# rfid_module_v2.net
KiCad netlist of a schematic drawn in EAGLE
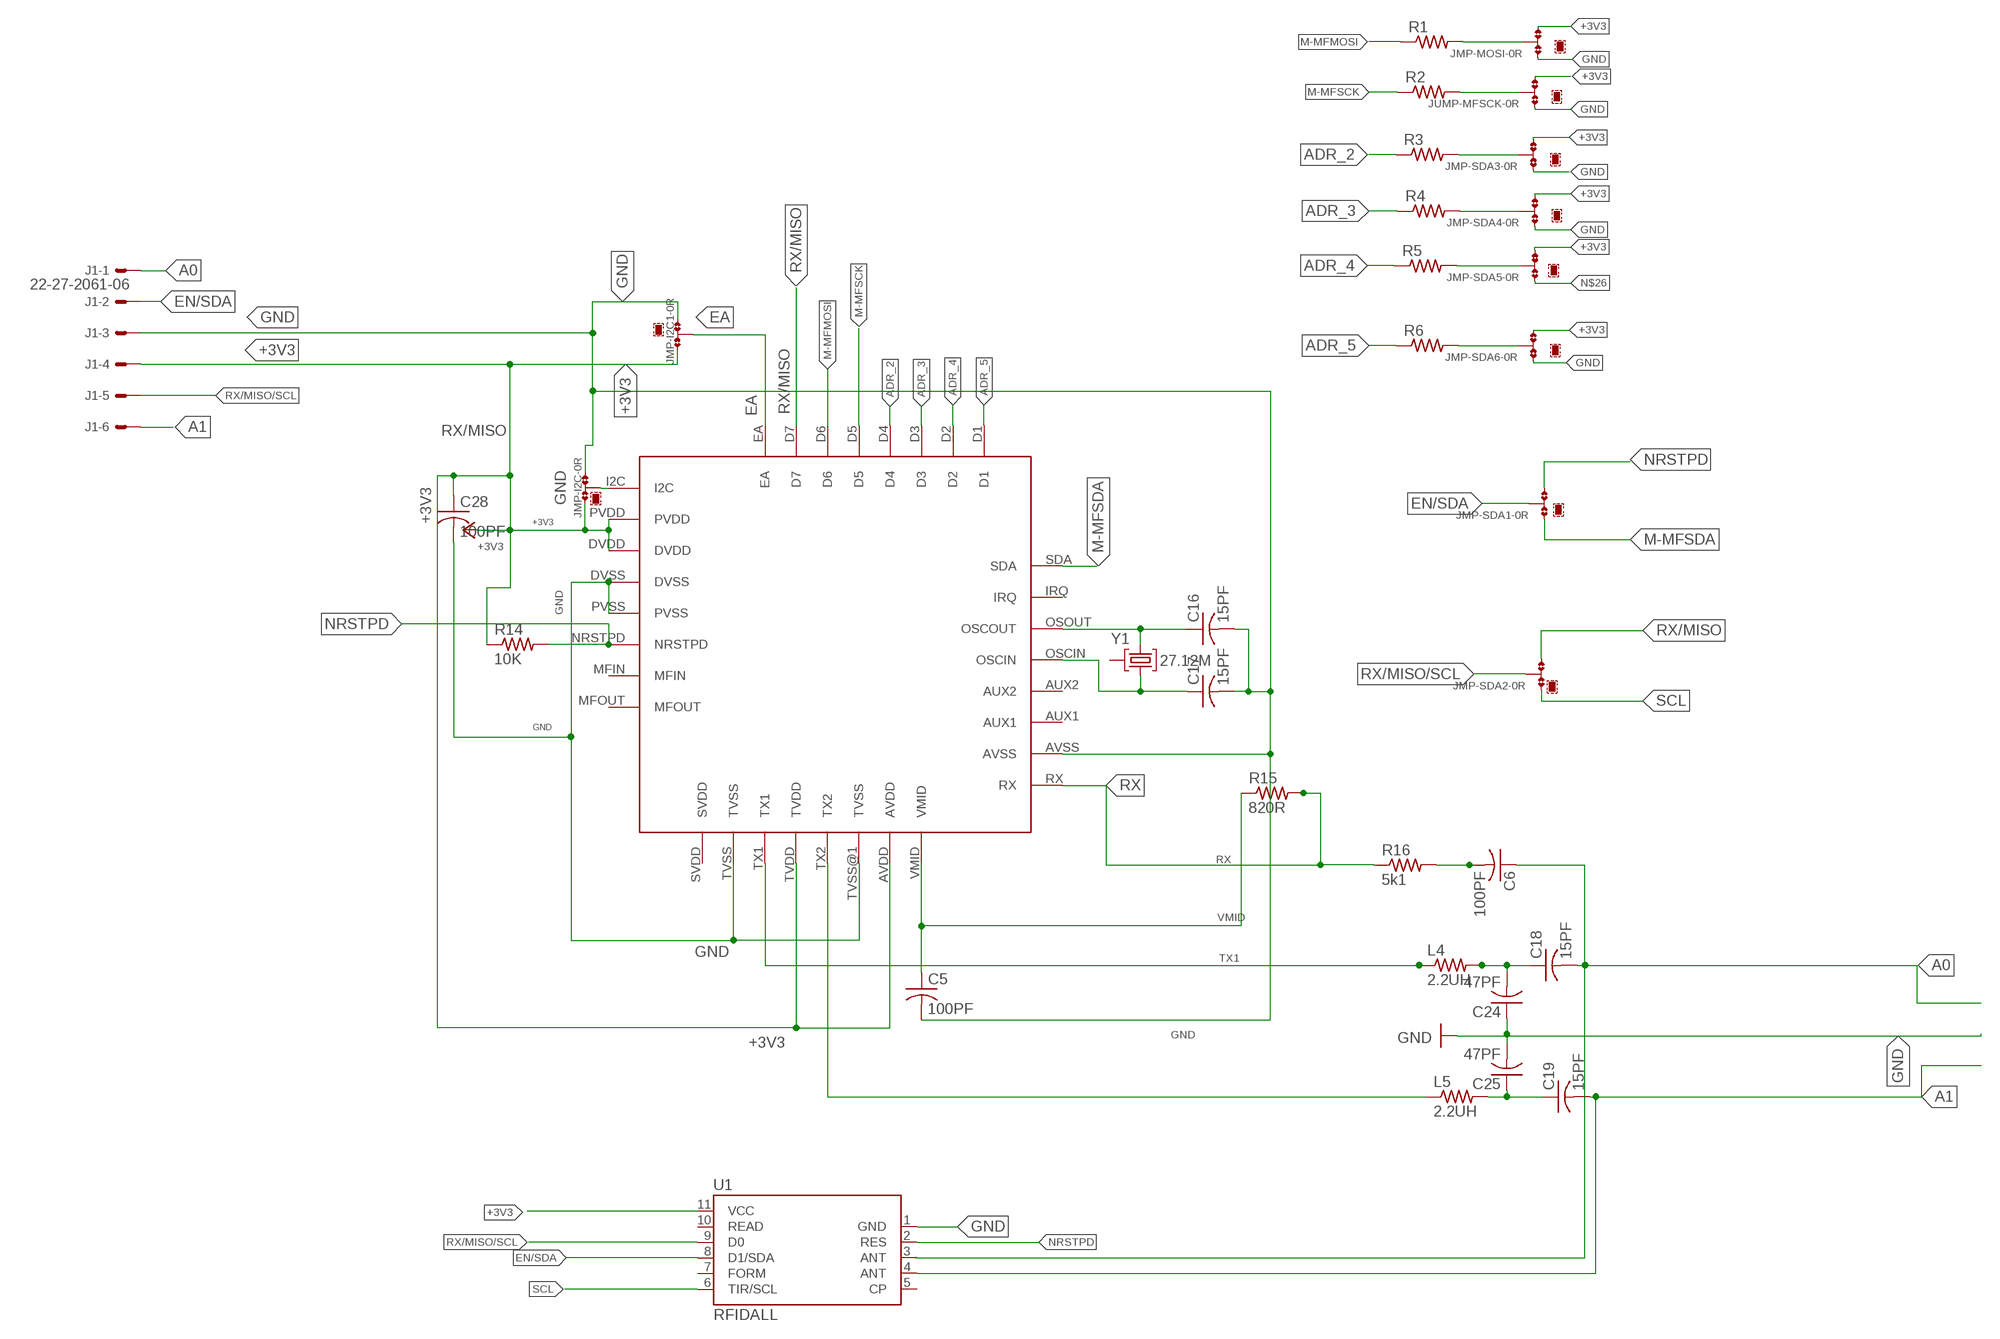
[diagram p0: schematic, sheet 1]

(export (version "E")
  (design (tool "Eeschema 10.0.6"))
  (components
    (comp (ref "C5")
      (value "100PF")
      (footprint "eagle-import:C0402")
      (libsource (lib "eagle-import") (part "C-USC0402"))
    )
    (comp (ref "C6")
      (value "100PF")
      (footprint "eagle-import:C0402")
      (libsource (lib "eagle-import") (part "C-USC0402"))
    )
    (comp (ref "C16")
      (value "15PF")
      (footprint "eagle-import:C0402")
      (libsource (lib "eagle-import") (part "C-USC0402"))
    )
    (comp (ref "C17")
      (value "15PF")
      (footprint "eagle-import:C0402")
      (libsource (lib "eagle-import") (part "C-USC0402"))
    )
    (comp (ref "C18")
      (value "15PF")
      (footprint "eagle-import:C0402")
      (libsource (lib "eagle-import") (part "C-USC0402"))
    )
    (comp (ref "C19")
      (value "15PF")
      (footprint "eagle-import:C0402")
      (libsource (lib "eagle-import") (part "C-USC0402"))
    )
    (comp (ref "C24")
      (value "47PF")
      (footprint "eagle-import:C0402")
      (libsource (lib "eagle-import") (part "C-USC0402"))
    )
    (comp (ref "C25")
      (value "47PF")
      (footprint "eagle-import:C0402")
      (libsource (lib "eagle-import") (part "C-USC0402"))
    )
    (comp (ref "C28")
      (value "100PF")
      (footprint "eagle-import:C0402")
      (libsource (lib "eagle-import") (part "C-USC0402"))
    )
    (comp (ref "J1")
      (value "22-27-2061-06")
      (footprint "eagle-import:6410-06")
      (libsource (lib "eagle-import") (part "22-?-0627-2061"))
    )
    (comp (ref "JMP-I2C")
      (value "0R-JUMPA")
      (footprint "eagle-import:A0R-JMP")
      (libsource (lib "eagle-import") (part "0R-JUMPA"))
    )
    (comp (ref "JMP-I2C1")
      (value "0R-JUMPA")
      (footprint "eagle-import:A0R-JMP")
      (libsource (lib "eagle-import") (part "0R-JUMPA"))
    )
    (comp (ref "JMP-MOSI")
      (value "0R-JUMPA")
      (footprint "eagle-import:A0R-JMP")
      (libsource (lib "eagle-import") (part "0R-JUMPA"))
    )
    (comp (ref "JMP-SDA1")
      (value "0R-JUMPA")
      (footprint "eagle-import:A0R-JMP")
      (libsource (lib "eagle-import") (part "0R-JUMPA"))
    )
    (comp (ref "JMP-SDA2")
      (value "0R-JUMPA")
      (footprint "eagle-import:A0R-JMP")
      (libsource (lib "eagle-import") (part "0R-JUMPA"))
    )
    (comp (ref "JMP-SDA3")
      (value "0R-JUMPA")
      (footprint "eagle-import:A0R-JMP")
      (libsource (lib "eagle-import") (part "0R-JUMPA"))
    )
    (comp (ref "JMP-SDA4")
      (value "0R-JUMPA")
      (footprint "eagle-import:A0R-JMP")
      (libsource (lib "eagle-import") (part "0R-JUMPA"))
    )
    (comp (ref "JMP-SDA5")
      (value "0R-JUMPA")
      (footprint "eagle-import:A0R-JMP")
      (libsource (lib "eagle-import") (part "0R-JUMPA"))
    )
    (comp (ref "JMP-SDA6")
      (value "0R-JUMPA")
      (footprint "eagle-import:A0R-JMP")
      (libsource (lib "eagle-import") (part "0R-JUMPA"))
    )
    (comp (ref "JUMP-MFSCK")
      (value "0R-JUMPA")
      (footprint "eagle-import:A0R-JMP")
      (libsource (lib "eagle-import") (part "0R-JUMPA"))
    )
    (comp (ref "L4")
      (value "2.2UH")
      (footprint "eagle-import:R0402")
      (libsource (lib "eagle-import") (part "R-US_R0402"))
    )
    (comp (ref "L5")
      (value "2.2UH")
      (footprint "eagle-import:R0402")
      (libsource (lib "eagle-import") (part "R-US_R0402"))
    )
    (comp (ref "R1")
      (value "R-US_R0402")
      (footprint "eagle-import:R0402")
      (libsource (lib "eagle-import") (part "R-US_R0402"))
    )
    (comp (ref "R2")
      (value "R-US_R0402")
      (footprint "eagle-import:R0402")
      (libsource (lib "eagle-import") (part "R-US_R0402"))
    )
    (comp (ref "R3")
      (value "R-US_R0402")
      (footprint "eagle-import:R0402")
      (libsource (lib "eagle-import") (part "R-US_R0402"))
    )
    (comp (ref "R4")
      (value "R-US_R0402")
      (footprint "eagle-import:R0402")
      (libsource (lib "eagle-import") (part "R-US_R0402"))
    )
    (comp (ref "R5")
      (value "R-US_R0402")
      (footprint "eagle-import:R0402")
      (libsource (lib "eagle-import") (part "R-US_R0402"))
    )
    (comp (ref "R6")
      (value "R-US_R0402")
      (footprint "eagle-import:R0402")
      (libsource (lib "eagle-import") (part "R-US_R0402"))
    )
    (comp (ref "R14")
      (value "10K")
      (footprint "eagle-import:R0402")
      (libsource (lib "eagle-import") (part "R-US_R0402"))
    )
    (comp (ref "R15")
      (value "820R")
      (footprint "eagle-import:R0402")
      (libsource (lib "eagle-import") (part "R-US_R0402"))
    )
    (comp (ref "R16")
      (value "5k1")
      (footprint "eagle-import:R0402")
      (libsource (lib "eagle-import") (part "R-US_R0402"))
    )
    (comp (ref "U$1")
      (value "MFRC522")
      (footprint "eagle-import:MFRC522")
      (libsource (lib "eagle-import") (part "MFRC522"))
    )
    (comp (ref "U1")
      (value "RFIDALL")
      (footprint "eagle-import:ID_PACKAGE")
      (libsource (lib "eagle-import") (part "RFIDALL"))
    )
    (comp (ref "Y1")
      (value "27.12M")
      (footprint "eagle-import:RAD3LEAD")
      (libsource (lib "eagle-import") (part "CRYSTAL"))
    )
  )
  (nets
    (net (code "1") (name "+3V3") (class "Default")
      (node (ref "C28") (pin "1") (pinfunction "1_1") (pintype "passive"))
      (node (ref "J1") (pin "4") (pinfunction "S_4") (pintype "passive"))
      (node (ref "JMP-I2C") (pin "3") (pinfunction "3_3") (pintype "passive"))
      (node (ref "JMP-I2C1") (pin "3") (pinfunction "3_3") (pintype "passive"))
      (node (ref "JMP-MOSI") (pin "3") (pinfunction "3_3") (pintype "passive"))
      (node (ref "JMP-SDA3") (pin "3") (pinfunction "3_3") (pintype "passive"))
      (node (ref "JMP-SDA4") (pin "3") (pinfunction "3_3") (pintype "passive"))
      (node (ref "JMP-SDA5") (pin "3") (pinfunction "3_3") (pintype "passive"))
      (node (ref "JMP-SDA6") (pin "3") (pinfunction "3_3") (pintype "passive"))
      (node (ref "JUMP-MFSCK") (pin "3") (pinfunction "3_3") (pintype "passive"))
      (node (ref "R14") (pin "1") (pinfunction "1_1") (pintype "passive"))
      (node (ref "U$1") (pin "AVDD") (pinfunction "AVDD_AVDD") (pintype "bidirectional"))
      (node (ref "U$1") (pin "DVDD") (pinfunction "DVDD_DVDD") (pintype "bidirectional"))
      (node (ref "U$1") (pin "PVDD") (pinfunction "PVDD_PVDD") (pintype "bidirectional"))
      (node (ref "U$1") (pin "TVDD") (pinfunction "TVDD_TVDD") (pintype "bidirectional"))
      (node (ref "U1") (pin "11") (pinfunction "VCC_11") (pintype "bidirectional"))
    )
    (net (code "2") (name "/TX1") (class "Default")
      (node (ref "L4") (pin "1") (pinfunction "1_1") (pintype "passive"))
      (node (ref "U$1") (pin "TX1") (pinfunction "TX1_TX1") (pintype "bidirectional"))
    )
    (net (code "3") (name "/VMID") (class "Default")
      (node (ref "C5") (pin "1") (pinfunction "1_1") (pintype "passive"))
      (node (ref "R15") (pin "1") (pinfunction "1_1") (pintype "passive"))
      (node (ref "U$1") (pin "VMID") (pinfunction "VMID_VMID") (pintype "bidirectional"))
    )
    (net (code "4") (name "A0") (class "Default")
      (node (ref "C18") (pin "2") (pinfunction "2_2") (pintype "passive"))
      (node (ref "C6") (pin "1") (pinfunction "1_1") (pintype "passive"))
      (node (ref "J1") (pin "1") (pinfunction "S_1") (pintype "passive"))
    )
    (net (code "5") (name "A1") (class "Default")
      (node (ref "C19") (pin "2") (pinfunction "2_2") (pintype "passive"))
      (node (ref "J1") (pin "6") (pinfunction "S_6") (pintype "passive"))
      (node (ref "U1") (pin "4") (pinfunction "ANT_4") (pintype "bidirectional"))
    )
    (net (code "6") (name "ADR_2") (class "Default")
      (node (ref "R3") (pin "1") (pinfunction "1_1") (pintype "passive"))
      (node (ref "U$1") (pin "D4") (pinfunction "D4_D4") (pintype "bidirectional"))
    )
    (net (code "7") (name "ADR_3") (class "Default")
      (node (ref "R4") (pin "1") (pinfunction "1_1") (pintype "passive"))
      (node (ref "U$1") (pin "D3") (pinfunction "D3_D3") (pintype "bidirectional"))
    )
    (net (code "8") (name "ADR_4") (class "Default")
      (node (ref "R5") (pin "1") (pinfunction "1_1") (pintype "passive"))
      (node (ref "U$1") (pin "D2") (pinfunction "D2_D2") (pintype "bidirectional"))
    )
    (net (code "9") (name "ADR_5") (class "Default")
      (node (ref "R6") (pin "1") (pinfunction "1_1") (pintype "passive"))
      (node (ref "U$1") (pin "D1") (pinfunction "D1_D1") (pintype "bidirectional"))
    )
    (net (code "10") (name "EA") (class "Default")
      (node (ref "JMP-I2C1") (pin "2") (pinfunction "2_2") (pintype "passive"))
      (node (ref "U$1") (pin "EA") (pinfunction "EA_EA") (pintype "bidirectional"))
    )
    (net (code "11") (name "EN{slash}SDA") (class "Default")
      (node (ref "J1") (pin "2") (pinfunction "S_2") (pintype "passive"))
      (node (ref "JMP-SDA1") (pin "2") (pinfunction "2_2") (pintype "passive"))
      (node (ref "U1") (pin "8") (pinfunction "D1/SDA_8") (pintype "bidirectional"))
    )
    (net (code "12") (name "GND") (class "Default")
      (node (ref "C16") (pin "2") (pinfunction "2_2") (pintype "passive"))
      (node (ref "C17") (pin "2") (pinfunction "2_2") (pintype "passive"))
      (node (ref "C24") (pin "1") (pinfunction "1_1") (pintype "passive"))
      (node (ref "C25") (pin "2") (pinfunction "2_2") (pintype "passive"))
      (node (ref "C28") (pin "2") (pinfunction "2_2") (pintype "passive"))
      (node (ref "C5") (pin "2") (pinfunction "2_2") (pintype "passive"))
      (node (ref "J1") (pin "3") (pinfunction "S_3") (pintype "passive"))
      (node (ref "JMP-I2C") (pin "1") (pinfunction "1_1") (pintype "passive"))
      (node (ref "JMP-I2C1") (pin "1") (pinfunction "1_1") (pintype "passive"))
      (node (ref "JMP-MOSI") (pin "1") (pinfunction "1_1") (pintype "passive"))
      (node (ref "JMP-SDA3") (pin "1") (pinfunction "1_1") (pintype "passive"))
      (node (ref "JMP-SDA4") (pin "1") (pinfunction "1_1") (pintype "passive"))
      (node (ref "JMP-SDA6") (pin "1") (pinfunction "1_1") (pintype "passive"))
      (node (ref "JUMP-MFSCK") (pin "1") (pinfunction "1_1") (pintype "passive"))
      (node (ref "U$1") (pin "AVSS") (pinfunction "AVSS_AVSS") (pintype "bidirectional"))
      (node (ref "U$1") (pin "DVSS") (pinfunction "DVSS_DVSS") (pintype "bidirectional"))
      (node (ref "U$1") (pin "PVSS") (pinfunction "PVSS_PVSS") (pintype "bidirectional"))
      (node (ref "U$1") (pin "TVSS") (pinfunction "TVSS_TVSS") (pintype "bidirectional"))
      (node (ref "U$1") (pin "TVSS@1") (pinfunction "TVSS_TVSS@1") (pintype "bidirectional"))
      (node (ref "U1") (pin "1") (pinfunction "GND_1") (pintype "bidirectional"))
    )
    (net (code "13") (name "M-MFMOSI") (class "Default")
      (node (ref "R1") (pin "1") (pinfunction "1_1") (pintype "passive"))
      (node (ref "U$1") (pin "D6") (pinfunction "D6_D6") (pintype "bidirectional"))
    )
    (net (code "14") (name "M-MFSCK") (class "Default")
      (node (ref "R2") (pin "1") (pinfunction "1_1") (pintype "passive"))
      (node (ref "U$1") (pin "D5") (pinfunction "D5_D5") (pintype "bidirectional"))
    )
    (net (code "15") (name "M-MFSDA") (class "Default")
      (node (ref "JMP-SDA1") (pin "1") (pinfunction "1_1") (pintype "passive"))
      (node (ref "U$1") (pin "SDA") (pinfunction "SDA_SDA") (pintype "bidirectional"))
    )
    (net (code "16") (name "N$26") (class "Default")
      (node (ref "JMP-SDA5") (pin "1") (pinfunction "1_1") (pintype "passive"))
    )
    (net (code "17") (name "NRSTPD") (class "Default")
      (node (ref "JMP-SDA1") (pin "3") (pinfunction "3_3") (pintype "passive"))
      (node (ref "R14") (pin "2") (pinfunction "2_2") (pintype "passive"))
      (node (ref "U$1") (pin "NRSTPD") (pinfunction "NRSTPD_NRSTPD") (pintype "bidirectional"))
      (node (ref "U1") (pin "2") (pinfunction "RES_2") (pintype "bidirectional"))
    )
    (net (code "18") (name "Net-(C6-Pad2)") (class "Default")
      (node (ref "C6") (pin "2") (pinfunction "2_2") (pintype "passive"))
      (node (ref "R16") (pin "2") (pinfunction "2_2") (pintype "passive"))
    )
    (net (code "19") (name "Net-(C17-Pad1)") (class "Default")
      (node (ref "C17") (pin "1") (pinfunction "1_1") (pintype "passive"))
      (node (ref "U$1") (pin "OSCIN") (pinfunction "OSCIN_OSCIN") (pintype "bidirectional"))
      (node (ref "Y1") (pin "1") (pinfunction "1_1") (pintype "passive"))
    )
    (net (code "20") (name "Net-(C18-Pad1)") (class "Default")
      (node (ref "C18") (pin "1") (pinfunction "1_1") (pintype "passive"))
      (node (ref "C24") (pin "2") (pinfunction "2_2") (pintype "passive"))
      (node (ref "L4") (pin "2") (pinfunction "2_2") (pintype "passive"))
    )
    (net (code "21") (name "Net-(C19-Pad1)") (class "Default")
      (node (ref "C19") (pin "1") (pinfunction "1_1") (pintype "passive"))
      (node (ref "C25") (pin "1") (pinfunction "1_1") (pintype "passive"))
      (node (ref "L5") (pin "2") (pinfunction "2_2") (pintype "passive"))
    )
    (net (code "22") (name "Net-(JMP-I2C-Pad2)") (class "Default")
      (node (ref "JMP-I2C") (pin "2") (pinfunction "2_2") (pintype "passive"))
      (node (ref "U$1") (pin "I2C") (pinfunction "I2C_I2C") (pintype "bidirectional"))
    )
    (net (code "23") (name "Net-(JMP-MOSI-Pad2)") (class "Default")
      (node (ref "JMP-MOSI") (pin "2") (pinfunction "2_2") (pintype "passive"))
      (node (ref "R1") (pin "2") (pinfunction "2_2") (pintype "passive"))
    )
    (net (code "24") (name "Net-(JMP-SDA3-Pad2)") (class "Default")
      (node (ref "JMP-SDA3") (pin "2") (pinfunction "2_2") (pintype "passive"))
      (node (ref "R3") (pin "2") (pinfunction "2_2") (pintype "passive"))
    )
    (net (code "25") (name "Net-(JMP-SDA4-Pad2)") (class "Default")
      (node (ref "JMP-SDA4") (pin "2") (pinfunction "2_2") (pintype "passive"))
      (node (ref "R4") (pin "2") (pinfunction "2_2") (pintype "passive"))
    )
    (net (code "26") (name "Net-(JMP-SDA5-Pad2)") (class "Default")
      (node (ref "JMP-SDA5") (pin "2") (pinfunction "2_2") (pintype "passive"))
      (node (ref "R5") (pin "2") (pinfunction "2_2") (pintype "passive"))
    )
    (net (code "27") (name "Net-(JMP-SDA6-Pad2)") (class "Default")
      (node (ref "JMP-SDA6") (pin "2") (pinfunction "2_2") (pintype "passive"))
      (node (ref "R6") (pin "2") (pinfunction "2_2") (pintype "passive"))
    )
    (net (code "28") (name "Net-(JUMP-MFSCK-Pad2)") (class "Default")
      (node (ref "JUMP-MFSCK") (pin "2") (pinfunction "2_2") (pintype "passive"))
      (node (ref "R2") (pin "2") (pinfunction "2_2") (pintype "passive"))
    )
    (net (code "29") (name "Net-(L5-Pad1)") (class "Default")
      (node (ref "L5") (pin "1") (pinfunction "1_1") (pintype "passive"))
      (node (ref "U$1") (pin "TX2") (pinfunction "TX2_TX2") (pintype "bidirectional"))
    )
    (net (code "30") (name "Net-(U$1-OSCOUT)") (class "Default")
      (node (ref "C16") (pin "1") (pinfunction "1_1") (pintype "passive"))
      (node (ref "U$1") (pin "OSOUT") (pinfunction "OSCOUT_OSOUT") (pintype "bidirectional"))
      (node (ref "Y1") (pin "3") (pinfunction "3_3") (pintype "passive"))
    )
    (net (code "31") (name "RX") (class "Default")
      (node (ref "R15") (pin "2") (pinfunction "2_2") (pintype "passive"))
      (node (ref "R16") (pin "1") (pinfunction "1_1") (pintype "passive"))
      (node (ref "U$1") (pin "RX") (pinfunction "RX_RX") (pintype "bidirectional"))
    )
    (net (code "32") (name "RX{slash}MISO") (class "Default")
      (node (ref "JMP-SDA2") (pin "3") (pinfunction "3_3") (pintype "passive"))
      (node (ref "U$1") (pin "D7") (pinfunction "D7_D7") (pintype "bidirectional"))
    )
    (net (code "33") (name "RX{slash}MISO{slash}SCL") (class "Default")
      (node (ref "J1") (pin "5") (pinfunction "S_5") (pintype "passive"))
      (node (ref "JMP-SDA2") (pin "2") (pinfunction "2_2") (pintype "passive"))
      (node (ref "U1") (pin "9") (pinfunction "D0_9") (pintype "bidirectional"))
    )
    (net (code "34") (name "SCL") (class "Default")
      (node (ref "JMP-SDA2") (pin "1") (pinfunction "1_1") (pintype "passive"))
      (node (ref "U1") (pin "6") (pinfunction "TIR/SCL_6") (pintype "bidirectional"))
    )
    (net (code "35") (name "unconnected-(U$1-PadAUX1)") (class "Default")
      (node (ref "U$1") (pin "AUX1") (pinfunction "AUX1_AUX1") (pintype "bidirectional"))
    )
    (net (code "36") (name "unconnected-(U$1-PadAUX2)") (class "Default")
      (node (ref "U$1") (pin "AUX2") (pinfunction "AUX2_AUX2") (pintype "bidirectional"))
    )
    (net (code "37") (name "unconnected-(U$1-PadIRQ)") (class "Default")
      (node (ref "U$1") (pin "IRQ") (pinfunction "IRQ_IRQ") (pintype "bidirectional"))
    )
    (net (code "38") (name "unconnected-(U$1-PadMFIN)") (class "Default")
      (node (ref "U$1") (pin "MFIN") (pinfunction "MFIN_MFIN") (pintype "bidirectional"))
    )
    (net (code "39") (name "unconnected-(U$1-PadMFOUT)") (class "Default")
      (node (ref "U$1") (pin "MFOUT") (pinfunction "MFOUT_MFOUT") (pintype "bidirectional"))
    )
    (net (code "40") (name "unconnected-(U$1-PadSVDD)") (class "Default")
      (node (ref "U$1") (pin "SVDD") (pinfunction "SVDD_SVDD") (pintype "bidirectional"))
    )
    (net (code "41") (name "unconnected-(U1-ANT-Pad3)") (class "Default")
      (node (ref "U1") (pin "3") (pinfunction "ANT_3") (pintype "bidirectional"))
    )
    (net (code "42") (name "unconnected-(U1-CP-Pad5)") (class "Default")
      (node (ref "U1") (pin "5") (pinfunction "CP_5") (pintype "bidirectional"))
    )
    (net (code "43") (name "unconnected-(U1-FORM-Pad7)") (class "Default")
      (node (ref "U1") (pin "7") (pinfunction "FORM_7") (pintype "bidirectional"))
    )
    (net (code "44") (name "unconnected-(U1-READ-Pad10)") (class "Default")
      (node (ref "U1") (pin "10") (pinfunction "READ_10") (pintype "bidirectional"))
    )
    (net (code "45") (name "unconnected-(Y1-Pad2)") (class "Default")
      (node (ref "Y1") (pin "2") (pinfunction "2_2") (pintype "passive"))
    )
  )
)
